# ARM_critter_prog_v01.net
KiCad netlist of a schematic drawn in EAGLE
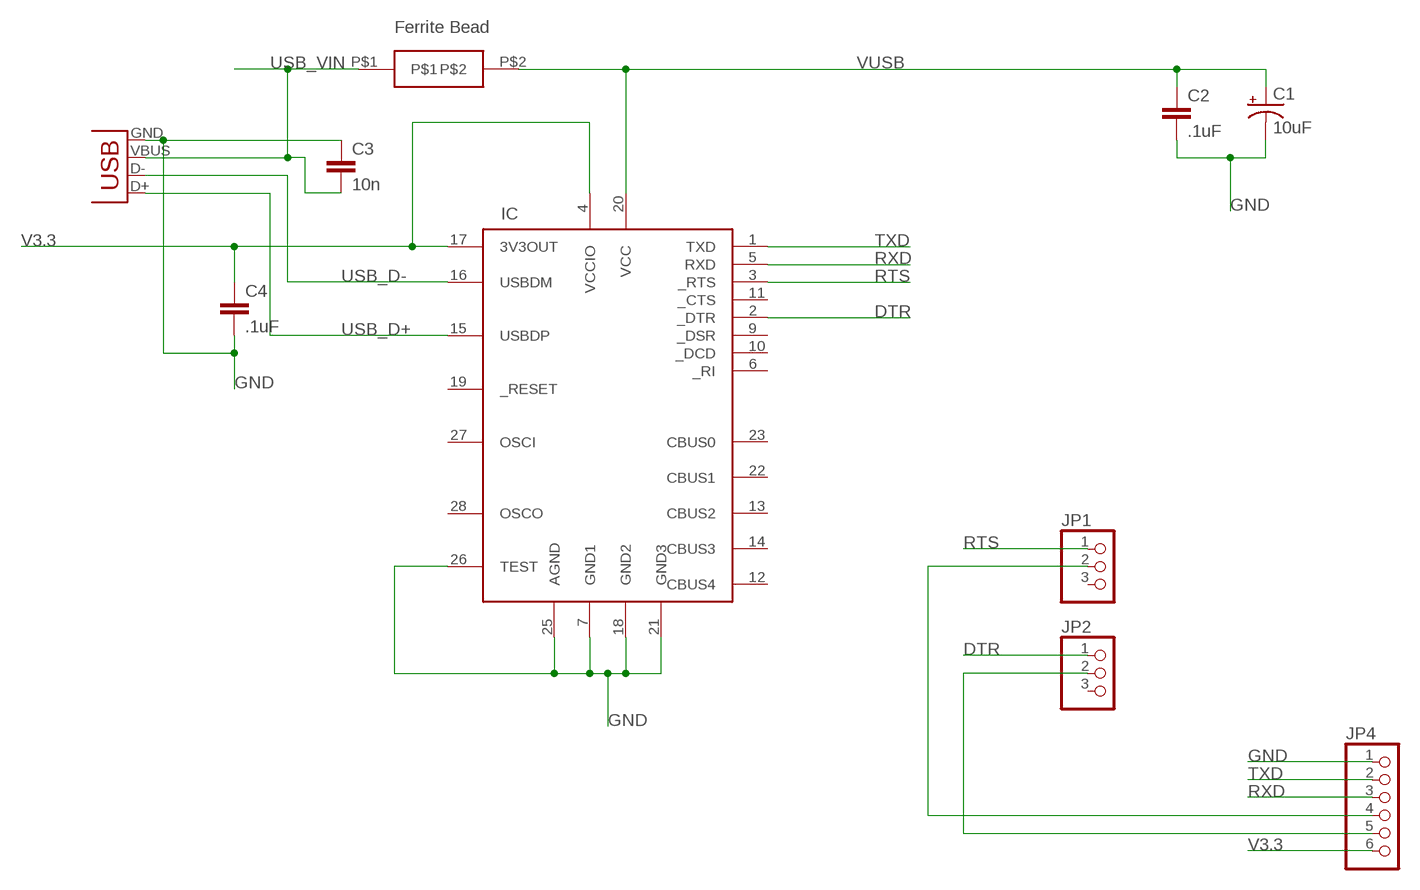
[diagram p0: schematic, sheet 1]

(export (version "E")
  (design (tool "Eeschema 10.0.6"))
  (components
    (comp (ref "C1")
      (value "10uF")
      (footprint "eagle-import:CPOL_1206")
      (libsource (lib "eagle-import") (part "CAP_POL1206"))
    )
    (comp (ref "C2")
      (value ".1uF")
      (footprint "eagle-import:C0603")
      (libsource (lib "eagle-import") (part "CAP0603"))
    )
    (comp (ref "C3")
      (value "10n")
      (footprint "eagle-import:C0603")
      (libsource (lib "eagle-import") (part "CAP0603"))
    )
    (comp (ref "C4")
      (value ".1uF")
      (footprint "eagle-import:C0603")
      (libsource (lib "eagle-import") (part "CAP0603"))
    )
    (comp (ref "IC")
      (value "FT232RL")
      (footprint "eagle-import:SSOP28DB")
      (libsource (lib "eagle-import") (part "FT232RL"))
    )
    (comp (ref "JP1")
      (value "PINHD-1X3")
      (footprint "eagle-import:1X03")
      (libsource (lib "eagle-import") (part "PINHD-1X3"))
    )
    (comp (ref "JP2")
      (value "PINHD-1X3")
      (footprint "eagle-import:1X03")
      (libsource (lib "eagle-import") (part "PINHD-1X3"))
    )
    (comp (ref "JP4")
      (value "PINHD-1X6")
      (footprint "eagle-import:1X06")
      (libsource (lib "eagle-import") (part "PINHD-1X6"))
    )
    (comp (ref "U$1")
      (value "FERRITE_BEAD")
      (footprint "eagle-import:FERRITE_BEAD")
      (libsource (lib "eagle-import") (part "FERRITE_BEAD"))
    )
    (comp (ref "X2")
      (value "USB-B-H")
      (footprint "eagle-import:USB-B-H")
      (libsource (lib "eagle-import") (part "USB-B-H"))
    )
  )
  (nets
    (net (code "1") (name "/DTR") (class "Default")
      (node (ref "IC") (pin "2") (pinfunction "_DTR_2") (pintype "output"))
      (node (ref "JP2") (pin "1") (pinfunction "1_1") (pintype "passive"))
    )
    (net (code "2") (name "/GND") (class "Default")
      (node (ref "C1") (pin "C") (pinfunction "-_C") (pintype "passive"))
      (node (ref "C2") (pin "2") (pinfunction "2_2") (pintype "passive"))
      (node (ref "C3") (pin "1") (pinfunction "1_1") (pintype "passive"))
      (node (ref "C4") (pin "2") (pinfunction "2_2") (pintype "passive"))
      (node (ref "IC") (pin "18") (pinfunction "GND2_18") (pintype "power_in"))
      (node (ref "IC") (pin "21") (pinfunction "GND3_21") (pintype "power_in"))
      (node (ref "IC") (pin "25") (pinfunction "AGND_25") (pintype "power_in"))
      (node (ref "IC") (pin "26") (pinfunction "TEST_26") (pintype "input"))
      (node (ref "IC") (pin "7") (pinfunction "GND1_7") (pintype "power_in"))
      (node (ref "JP4") (pin "1") (pinfunction "1_1") (pintype "passive"))
      (node (ref "X2") (pin "GND") (pinfunction "GND_GND") (pintype "bidirectional"))
    )
    (net (code "3") (name "/RTS") (class "Default")
      (node (ref "IC") (pin "3") (pinfunction "_RTS_3") (pintype "output"))
      (node (ref "JP1") (pin "1") (pinfunction "1_1") (pintype "passive"))
    )
    (net (code "4") (name "/RXD") (class "Default")
      (node (ref "IC") (pin "5") (pinfunction "RXD_5") (pintype "input"))
      (node (ref "JP4") (pin "3") (pinfunction "3_3") (pintype "passive"))
    )
    (net (code "5") (name "/TXD") (class "Default")
      (node (ref "IC") (pin "1") (pinfunction "TXD_1") (pintype "output"))
      (node (ref "JP4") (pin "2") (pinfunction "2_2") (pintype "passive"))
    )
    (net (code "6") (name "/USB_D+") (class "Default")
      (node (ref "IC") (pin "15") (pinfunction "USBDP_15") (pintype "bidirectional"))
      (node (ref "X2") (pin "D+") (pinfunction "D+_D+") (pintype "bidirectional"))
    )
    (net (code "7") (name "/USB_D-") (class "Default")
      (node (ref "IC") (pin "16") (pinfunction "USBDM_16") (pintype "bidirectional"))
      (node (ref "X2") (pin "D-") (pinfunction "D-_D-") (pintype "bidirectional"))
    )
    (net (code "8") (name "/USB_VIN") (class "Default")
      (node (ref "C3") (pin "2") (pinfunction "2_2") (pintype "passive"))
      (node (ref "U$1") (pin "P$1") (pinfunction "P$1_P$1") (pintype "bidirectional"))
      (node (ref "X2") (pin "VBUS") (pinfunction "VBUS_VBUS") (pintype "bidirectional"))
    )
    (net (code "9") (name "/V3.3") (class "Default")
      (node (ref "C4") (pin "1") (pinfunction "1_1") (pintype "passive"))
      (node (ref "IC") (pin "17") (pinfunction "3V3OUT_17") (pintype "output"))
      (node (ref "IC") (pin "4") (pinfunction "VCCIO_4") (pintype "power_in"))
      (node (ref "JP4") (pin "6") (pinfunction "6_6") (pintype "passive"))
    )
    (net (code "10") (name "/VUSB") (class "Default")
      (node (ref "C1") (pin "A") (pinfunction "+_A") (pintype "passive"))
      (node (ref "C2") (pin "1") (pinfunction "1_1") (pintype "passive"))
      (node (ref "IC") (pin "20") (pinfunction "VCC_20") (pintype "power_in"))
      (node (ref "U$1") (pin "P$2") (pinfunction "P$2_P$2") (pintype "bidirectional"))
    )
    (net (code "11") (name "Net-(JP1-Pad2)") (class "Default")
      (node (ref "JP1") (pin "2") (pinfunction "2_2") (pintype "passive"))
      (node (ref "JP4") (pin "4") (pinfunction "4_4") (pintype "passive"))
    )
    (net (code "12") (name "Net-(JP2-Pad2)") (class "Default")
      (node (ref "JP2") (pin "2") (pinfunction "2_2") (pintype "passive"))
      (node (ref "JP4") (pin "5") (pinfunction "5_5") (pintype "passive"))
    )
    (net (code "13") (name "unconnected-(IC-CBUS0-Pad23)") (class "Default")
      (node (ref "IC") (pin "23") (pinfunction "CBUS0_23") (pintype "bidirectional"))
    )
    (net (code "14") (name "unconnected-(IC-CBUS1-Pad22)") (class "Default")
      (node (ref "IC") (pin "22") (pinfunction "CBUS1_22") (pintype "bidirectional"))
    )
    (net (code "15") (name "unconnected-(IC-CBUS2-Pad13)") (class "Default")
      (node (ref "IC") (pin "13") (pinfunction "CBUS2_13") (pintype "bidirectional"))
    )
    (net (code "16") (name "unconnected-(IC-CBUS3-Pad14)") (class "Default")
      (node (ref "IC") (pin "14") (pinfunction "CBUS3_14") (pintype "bidirectional"))
    )
    (net (code "17") (name "unconnected-(IC-CBUS4-Pad12)") (class "Default")
      (node (ref "IC") (pin "12") (pinfunction "CBUS4_12") (pintype "bidirectional"))
    )
    (net (code "18") (name "unconnected-(IC-OSCI-Pad27)") (class "Default")
      (node (ref "IC") (pin "27") (pinfunction "OSCI_27") (pintype "input"))
    )
    (net (code "19") (name "unconnected-(IC-OSCO-Pad28)") (class "Default")
      (node (ref "IC") (pin "28") (pinfunction "OSCO_28") (pintype "output"))
    )
    (net (code "20") (name "unconnected-(IC-_CTS-Pad11)") (class "Default")
      (node (ref "IC") (pin "11") (pinfunction "_CTS_11") (pintype "input"))
    )
    (net (code "21") (name "unconnected-(IC-_DCD-Pad10)") (class "Default")
      (node (ref "IC") (pin "10") (pinfunction "_DCD_10") (pintype "input"))
    )
    (net (code "22") (name "unconnected-(IC-_DSR-Pad9)") (class "Default")
      (node (ref "IC") (pin "9") (pinfunction "_DSR_9") (pintype "input"))
    )
    (net (code "23") (name "unconnected-(IC-_RESET-Pad19)") (class "Default")
      (node (ref "IC") (pin "19") (pinfunction "_RESET_19") (pintype "input"))
    )
    (net (code "24") (name "unconnected-(IC-_RI-Pad6)") (class "Default")
      (node (ref "IC") (pin "6") (pinfunction "_RI_6") (pintype "input"))
    )
    (net (code "25") (name "unconnected-(JP1-Pad3)") (class "Default")
      (node (ref "JP1") (pin "3") (pinfunction "3_3") (pintype "passive"))
    )
    (net (code "26") (name "unconnected-(JP2-Pad3)") (class "Default")
      (node (ref "JP2") (pin "3") (pinfunction "3_3") (pintype "passive"))
    )
  )
)
